# avr_programming_shield_Zif.net
KiCad netlist of a schematic drawn in EAGLE
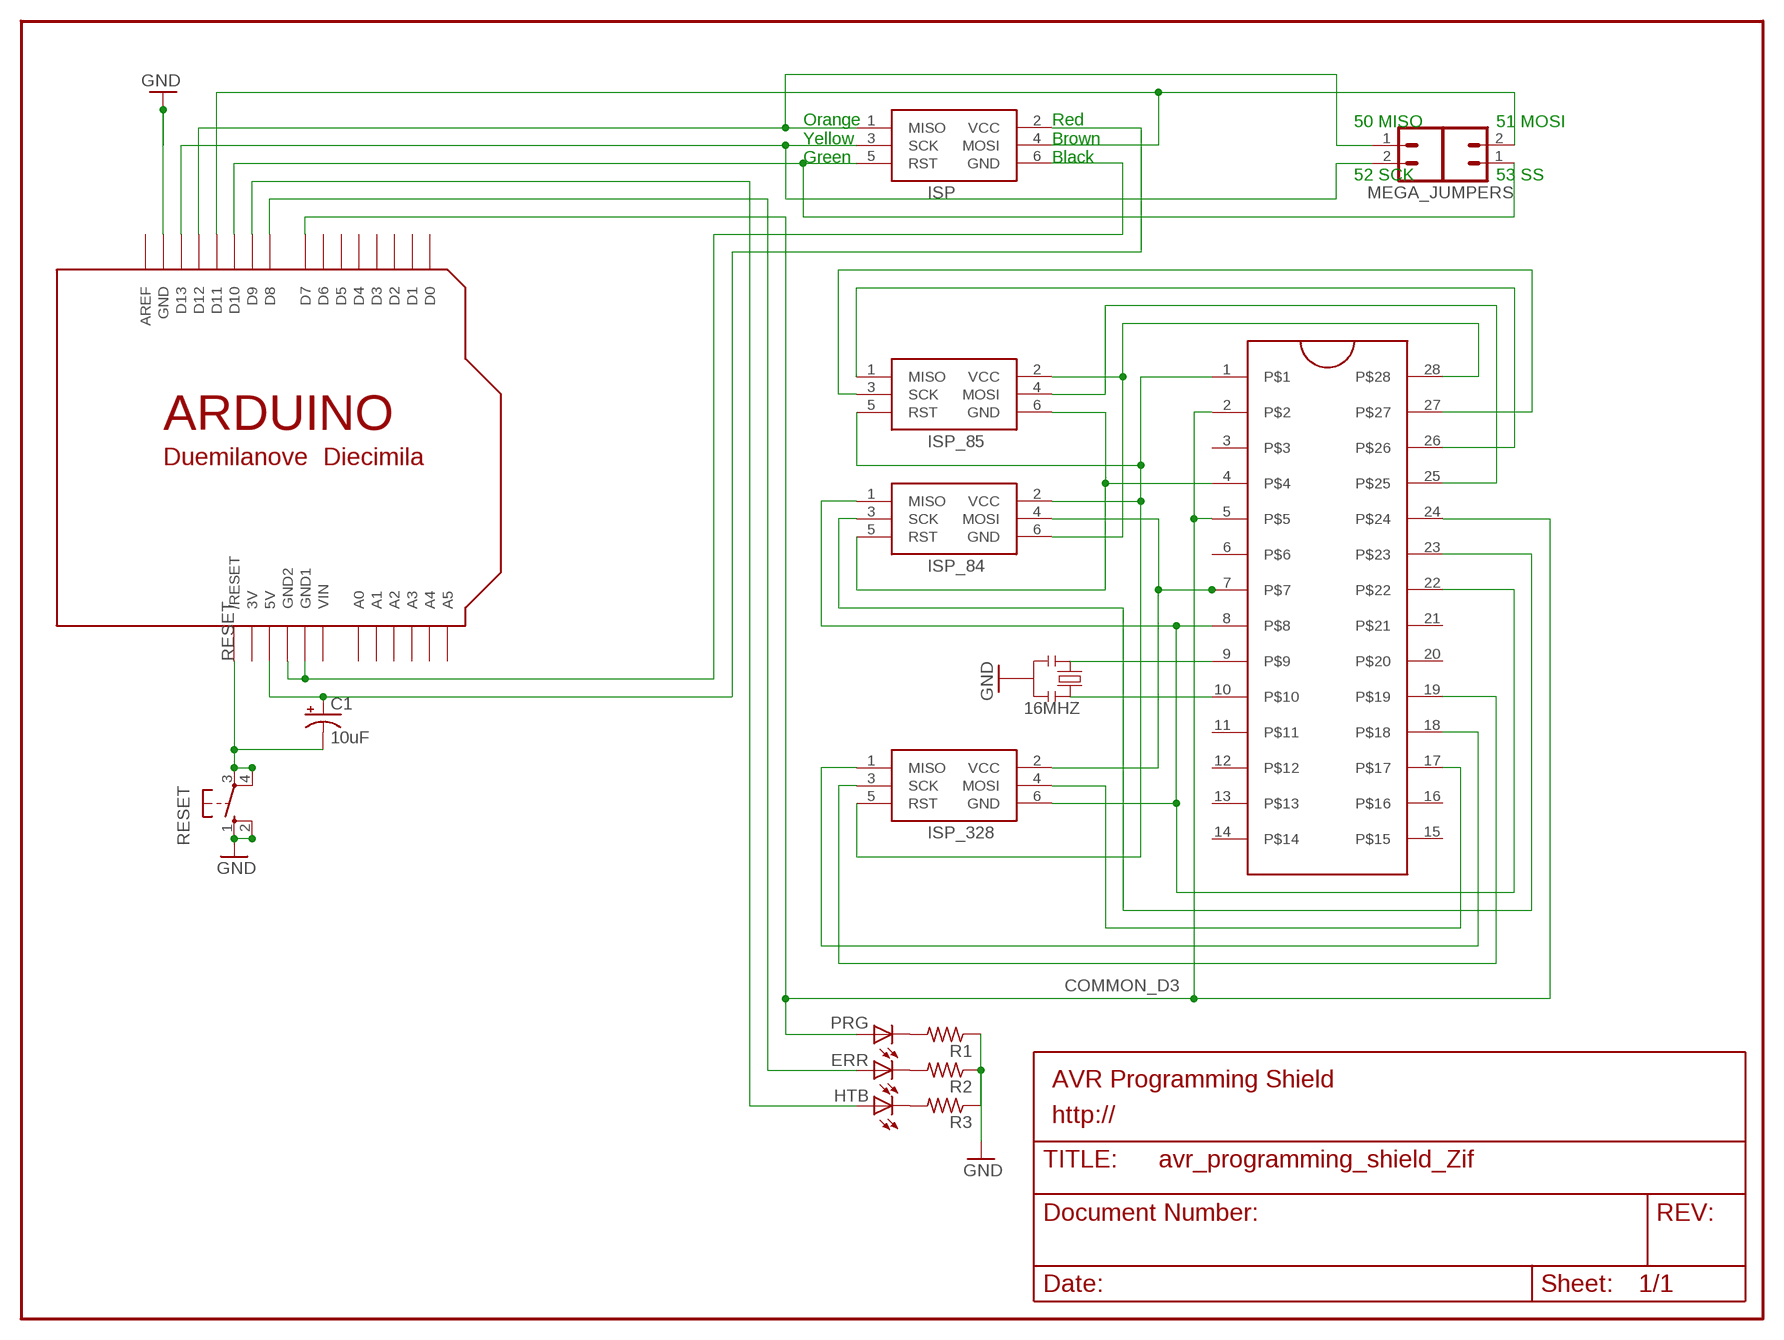
[diagram p0: schematic, sheet 1]

(export (version "E")
  (design (tool "Eeschema 10.0.6"))
  (components
    (comp (ref "16MHZ")
      (value "RESONATORPTH")
      (footprint "eagle-import:RESONATOR-PTH")
      (libsource (lib "eagle-import") (part "RESONATORPTH"))
    )
    (comp (ref "C1")
      (value "10uF")
      (footprint "eagle-import:CPOL-RADIAL-10UF-25V")
      (libsource (lib "eagle-import") (part "CAP_POLPTH2"))
    )
    (comp (ref "ERR")
      (value "LED3MM")
      (footprint "eagle-import:LED3MM")
      (libsource (lib "eagle-import") (part "LED3MM"))
    )
    (comp (ref "HTB")
      (value "LED3MM")
      (footprint "eagle-import:LED3MM")
      (libsource (lib "eagle-import") (part "LED3MM"))
    )
    (comp (ref "ISP")
      (value "AVRISP-6")
      (footprint "eagle-import:AVRISP")
      (libsource (lib "eagle-import") (part "AVRISP-6"))
    )
    (comp (ref "ISP_84")
      (value "AVRISP-6")
      (footprint "eagle-import:AVRISP")
      (libsource (lib "eagle-import") (part "AVRISP-6"))
    )
    (comp (ref "ISP_85")
      (value "AVRISP-6")
      (footprint "eagle-import:AVRISP")
      (libsource (lib "eagle-import") (part "AVRISP-6"))
    )
    (comp (ref "ISP_328")
      (value "AVRISP-6")
      (footprint "eagle-import:AVRISP")
      (libsource (lib "eagle-import") (part "AVRISP-6"))
    )
    (comp (ref "JP2")
      (value "M02PTH")
      (footprint "eagle-import:1X02")
      (libsource (lib "eagle-import") (part "M02PTH"))
    )
    (comp (ref "MEGA_JUMPERS")
      (value "M02PTH")
      (footprint "eagle-import:1X02")
      (libsource (lib "eagle-import") (part "M02PTH"))
    )
    (comp (ref "PRG")
      (value "LED3MM")
      (footprint "eagle-import:LED3MM")
      (libsource (lib "eagle-import") (part "LED3MM"))
    )
    (comp (ref "R1")
      (value "R-US_0204/2V")
      (footprint "eagle-import:0204V")
      (libsource (lib "eagle-import") (part "R-US_0204/2V"))
    )
    (comp (ref "R2")
      (value "R-US_0204/2V")
      (footprint "eagle-import:0204V")
      (libsource (lib "eagle-import") (part "R-US_0204/2V"))
    )
    (comp (ref "R3")
      (value "R-US_0204/2V")
      (footprint "eagle-import:0204V")
      (libsource (lib "eagle-import") (part "R-US_0204/2V"))
    )
    (comp (ref "RESET")
      (value "10-XX")
      (footprint "eagle-import:B3F-10XX")
      (libsource (lib "eagle-import") (part "10-XX"))
    )
    (comp (ref "U$1")
      (value "ARDUINO-NOHOLE")
      (footprint "eagle-import:ARDUINO-NOHOLE")
      (libsource (lib "eagle-import") (part "ARDUINO-NOHOLE"))
    )
    (comp (ref "U$2")
      (value "ZIFSOCKET-28-3ZIFFSOCKET-28-3")
      (footprint "eagle-import:DIL28-3-ZIF_SOCKET")
      (libsource (lib "eagle-import") (part "ZIFSOCKET-28-3ZIFFSOCKET-28-3"))
    )
  )
  (nets
    (net (code "1") (name "/3V") (class "Default")
      (node (ref "U$1") (pin "3V") (pinfunction "3V_3V") (pintype "power_in"))
    )
    (net (code "2") (name "/COMMON_D3") (class "Default")
      (node (ref "PRG") (pin "A") (pinfunction "A_A") (pintype "passive"))
      (node (ref "U$1") (pin "D7") (pinfunction "D7_D7") (pintype "bidirectional"))
      (node (ref "U$2") (pin "2") (pinfunction "P$2_2") (pintype "bidirectional"))
      (node (ref "U$2") (pin "24") (pinfunction "P$24_24") (pintype "bidirectional"))
      (node (ref "U$2") (pin "5") (pinfunction "P$5_5") (pintype "bidirectional"))
    )
    (net (code "3") (name "/RESET") (class "Default")
      (node (ref "C1") (pin "2") (pinfunction "-_2") (pintype "passive"))
      (node (ref "RESET") (pin "3") (pinfunction "P_3") (pintype "passive"))
      (node (ref "RESET") (pin "4") (pinfunction "P1_4") (pintype "passive"))
      (node (ref "U$1") (pin "RESET") (pinfunction "/RESET_RESET") (pintype "bidirectional"))
    )
    (net (code "4") (name "/VIN") (class "Default")
      (node (ref "U$1") (pin "VIN") (pinfunction "VIN_VIN") (pintype "power_in"))
    )
    (net (code "5") (name "GND") (class "Default")
      (node (ref "16MHZ") (pin "2") (pinfunction "2_2") (pintype "passive"))
      (node (ref "ISP") (pin "6") (pinfunction "GND_6") (pintype "power_in"))
      (node (ref "R1") (pin "1") (pinfunction "1_1") (pintype "passive"))
      (node (ref "R2") (pin "1") (pinfunction "1_1") (pintype "passive"))
      (node (ref "R3") (pin "1") (pinfunction "1_1") (pintype "passive"))
      (node (ref "RESET") (pin "1") (pinfunction "S_1") (pintype "passive"))
      (node (ref "RESET") (pin "2") (pinfunction "S1_2") (pintype "passive"))
      (node (ref "U$1") (pin "GND") (pinfunction "GND_GND") (pintype "power_in"))
      (node (ref "U$1") (pin "GND1") (pinfunction "GND1_GND1") (pintype "power_in"))
      (node (ref "U$1") (pin "GND2") (pinfunction "GND2_GND2") (pintype "power_in"))
    )
    (net (code "6") (name "Net-(C1-+)") (class "Default")
      (node (ref "C1") (pin "1") (pinfunction "+_1") (pintype "passive"))
      (node (ref "ISP") (pin "2") (pinfunction "VCC_2") (pintype "power_in"))
      (node (ref "U$1") (pin "5V") (pinfunction "5V_5V") (pintype "power_in"))
    )
    (net (code "7") (name "Net-(ERR-C)") (class "Default")
      (node (ref "ERR") (pin "K") (pinfunction "C_K") (pintype "passive"))
      (node (ref "R2") (pin "2") (pinfunction "2_2") (pintype "passive"))
    )
    (net (code "8") (name "Net-(ERR-PadA)") (class "Default")
      (node (ref "ERR") (pin "A") (pinfunction "A_A") (pintype "passive"))
      (node (ref "U$1") (pin "D8") (pinfunction "D8_D8") (pintype "bidirectional"))
    )
    (net (code "9") (name "Net-(HTB-C)") (class "Default")
      (node (ref "HTB") (pin "K") (pinfunction "C_K") (pintype "passive"))
      (node (ref "R3") (pin "2") (pinfunction "2_2") (pintype "passive"))
    )
    (net (code "10") (name "Net-(HTB-PadA)") (class "Default")
      (node (ref "HTB") (pin "A") (pinfunction "A_A") (pintype "passive"))
      (node (ref "U$1") (pin "D9") (pinfunction "D9_D9") (pintype "bidirectional"))
    )
    (net (code "11") (name "Net-(ISP-MISO)") (class "Default")
      (node (ref "ISP") (pin "1") (pinfunction "MISO_1") (pintype "input"))
      (node (ref "MEGA_JUMPERS") (pin "1") (pinfunction "1_1") (pintype "passive"))
      (node (ref "U$1") (pin "D12") (pinfunction "D12_D12") (pintype "bidirectional"))
    )
    (net (code "12") (name "Net-(ISP-MOSI)") (class "Default")
      (node (ref "ISP") (pin "4") (pinfunction "MOSI_4") (pintype "output"))
      (node (ref "JP2") (pin "2") (pinfunction "2_2") (pintype "passive"))
      (node (ref "U$1") (pin "D11") (pinfunction "D11_D11") (pintype "bidirectional"))
    )
    (net (code "13") (name "Net-(ISP-RST)") (class "Default")
      (node (ref "ISP") (pin "5") (pinfunction "RST_5") (pintype "output"))
      (node (ref "JP2") (pin "1") (pinfunction "1_1") (pintype "passive"))
      (node (ref "U$1") (pin "D10") (pinfunction "D10_D10") (pintype "bidirectional"))
    )
    (net (code "14") (name "Net-(ISP-SCK)") (class "Default")
      (node (ref "ISP") (pin "3") (pinfunction "SCK_3") (pintype "output"))
      (node (ref "MEGA_JUMPERS") (pin "2") (pinfunction "2_2") (pintype "passive"))
      (node (ref "U$1") (pin "D13") (pinfunction "D13_D13") (pintype "bidirectional"))
    )
    (net (code "15") (name "Net-(ISP_84-GND)") (class "Default")
      (node (ref "ISP_84") (pin "6") (pinfunction "GND_6") (pintype "power_in"))
      (node (ref "ISP_85") (pin "2") (pinfunction "VCC_2") (pintype "power_in"))
      (node (ref "U$2") (pin "28") (pinfunction "P$28_28") (pintype "bidirectional"))
    )
    (net (code "16") (name "Net-(ISP_84-RST)") (class "Default")
      (node (ref "ISP_84") (pin "5") (pinfunction "RST_5") (pintype "output"))
      (node (ref "ISP_85") (pin "6") (pinfunction "GND_6") (pintype "power_in"))
      (node (ref "U$2") (pin "4") (pinfunction "P$4_4") (pintype "bidirectional"))
    )
    (net (code "17") (name "Net-(ISP_84-SCK)") (class "Default")
      (node (ref "ISP_84") (pin "3") (pinfunction "SCK_3") (pintype "output"))
      (node (ref "U$2") (pin "23") (pinfunction "P$23_23") (pintype "bidirectional"))
    )
    (net (code "18") (name "Net-(ISP_85-MISO)") (class "Default")
      (node (ref "ISP_85") (pin "1") (pinfunction "MISO_1") (pintype "input"))
      (node (ref "U$2") (pin "26") (pinfunction "P$26_26") (pintype "bidirectional"))
    )
    (net (code "19") (name "Net-(ISP_85-MOSI)") (class "Default")
      (node (ref "ISP_85") (pin "4") (pinfunction "MOSI_4") (pintype "output"))
      (node (ref "U$2") (pin "25") (pinfunction "P$25_25") (pintype "bidirectional"))
    )
    (net (code "20") (name "Net-(ISP_85-SCK)") (class "Default")
      (node (ref "ISP_85") (pin "3") (pinfunction "SCK_3") (pintype "output"))
      (node (ref "U$2") (pin "27") (pinfunction "P$27_27") (pintype "bidirectional"))
    )
    (net (code "21") (name "Net-(ISP_328-GND)") (class "Default")
      (node (ref "ISP_328") (pin "6") (pinfunction "GND_6") (pintype "power_in"))
      (node (ref "ISP_84") (pin "1") (pinfunction "MISO_1") (pintype "input"))
      (node (ref "U$2") (pin "22") (pinfunction "P$22_22") (pintype "bidirectional"))
      (node (ref "U$2") (pin "8") (pinfunction "P$8_8") (pintype "bidirectional"))
    )
    (net (code "22") (name "Net-(ISP_328-MISO)") (class "Default")
      (node (ref "ISP_328") (pin "1") (pinfunction "MISO_1") (pintype "input"))
      (node (ref "U$2") (pin "18") (pinfunction "P$18_18") (pintype "bidirectional"))
    )
    (net (code "23") (name "Net-(ISP_328-MOSI)") (class "Default")
      (node (ref "ISP_328") (pin "4") (pinfunction "MOSI_4") (pintype "output"))
      (node (ref "U$2") (pin "17") (pinfunction "P$17_17") (pintype "bidirectional"))
    )
    (net (code "24") (name "Net-(ISP_328-RST)") (class "Default")
      (node (ref "ISP_328") (pin "5") (pinfunction "RST_5") (pintype "output"))
      (node (ref "ISP_84") (pin "2") (pinfunction "VCC_2") (pintype "power_in"))
      (node (ref "ISP_85") (pin "5") (pinfunction "RST_5") (pintype "output"))
      (node (ref "U$2") (pin "1") (pinfunction "P$1_1") (pintype "bidirectional"))
    )
    (net (code "25") (name "Net-(ISP_328-SCK)") (class "Default")
      (node (ref "ISP_328") (pin "3") (pinfunction "SCK_3") (pintype "output"))
      (node (ref "U$2") (pin "19") (pinfunction "P$19_19") (pintype "bidirectional"))
    )
    (net (code "26") (name "Net-(ISP_328-VCC)") (class "Default")
      (node (ref "ISP_328") (pin "2") (pinfunction "VCC_2") (pintype "power_in"))
      (node (ref "ISP_84") (pin "4") (pinfunction "MOSI_4") (pintype "output"))
      (node (ref "U$2") (pin "7") (pinfunction "P$7_7") (pintype "bidirectional"))
    )
    (net (code "27") (name "Net-(PRG-C)") (class "Default")
      (node (ref "PRG") (pin "K") (pinfunction "C_K") (pintype "passive"))
      (node (ref "R1") (pin "2") (pinfunction "2_2") (pintype "passive"))
    )
    (net (code "28") (name "Net-(U$2-P$9)") (class "Default")
      (node (ref "16MHZ") (pin "1") (pinfunction "1_1") (pintype "passive"))
      (node (ref "U$2") (pin "9") (pinfunction "P$9_9") (pintype "bidirectional"))
    )
    (net (code "29") (name "Net-(U$2-P$10)") (class "Default")
      (node (ref "16MHZ") (pin "3") (pinfunction "3_3") (pintype "passive"))
      (node (ref "U$2") (pin "10") (pinfunction "P$10_10") (pintype "bidirectional"))
    )
    (net (code "30") (name "unconnected-(U$1-PadA0)") (class "Default")
      (node (ref "U$1") (pin "A0") (pinfunction "A0_A0") (pintype "bidirectional"))
    )
    (net (code "31") (name "unconnected-(U$1-PadA1)") (class "Default")
      (node (ref "U$1") (pin "A1") (pinfunction "A1_A1") (pintype "bidirectional"))
    )
    (net (code "32") (name "unconnected-(U$1-PadA2)") (class "Default")
      (node (ref "U$1") (pin "A2") (pinfunction "A2_A2") (pintype "bidirectional"))
    )
    (net (code "33") (name "unconnected-(U$1-PadA3)") (class "Default")
      (node (ref "U$1") (pin "A3") (pinfunction "A3_A3") (pintype "bidirectional"))
    )
    (net (code "34") (name "unconnected-(U$1-PadA4)") (class "Default")
      (node (ref "U$1") (pin "A4") (pinfunction "A4_A4") (pintype "bidirectional"))
    )
    (net (code "35") (name "unconnected-(U$1-PadA5)") (class "Default")
      (node (ref "U$1") (pin "A5") (pinfunction "A5_A5") (pintype "bidirectional"))
    )
    (net (code "36") (name "unconnected-(U$1-PadAREF)") (class "Default")
      (node (ref "U$1") (pin "AREF") (pinfunction "AREF_AREF") (pintype "bidirectional"))
    )
    (net (code "37") (name "unconnected-(U$1-PadD0)") (class "Default")
      (node (ref "U$1") (pin "D0") (pinfunction "D0_D0") (pintype "bidirectional"))
    )
    (net (code "38") (name "unconnected-(U$1-PadD1)") (class "Default")
      (node (ref "U$1") (pin "D1") (pinfunction "D1_D1") (pintype "bidirectional"))
    )
    (net (code "39") (name "unconnected-(U$1-PadD2)") (class "Default")
      (node (ref "U$1") (pin "D2") (pinfunction "D2_D2") (pintype "bidirectional"))
    )
    (net (code "40") (name "unconnected-(U$1-PadD3)") (class "Default")
      (node (ref "U$1") (pin "D3") (pinfunction "D3_D3") (pintype "bidirectional"))
    )
    (net (code "41") (name "unconnected-(U$1-PadD4)") (class "Default")
      (node (ref "U$1") (pin "D4") (pinfunction "D4_D4") (pintype "bidirectional"))
    )
    (net (code "42") (name "unconnected-(U$1-PadD5)") (class "Default")
      (node (ref "U$1") (pin "D5") (pinfunction "D5_D5") (pintype "bidirectional"))
    )
    (net (code "43") (name "unconnected-(U$1-PadD6)") (class "Default")
      (node (ref "U$1") (pin "D6") (pinfunction "D6_D6") (pintype "bidirectional"))
    )
    (net (code "44") (name "unconnected-(U$2-P$3-Pad3)") (class "Default")
      (node (ref "U$2") (pin "3") (pinfunction "P$3_3") (pintype "bidirectional"))
    )
    (net (code "45") (name "unconnected-(U$2-P$6-Pad6)") (class "Default")
      (node (ref "U$2") (pin "6") (pinfunction "P$6_6") (pintype "bidirectional"))
    )
    (net (code "46") (name "unconnected-(U$2-P$11-Pad11)") (class "Default")
      (node (ref "U$2") (pin "11") (pinfunction "P$11_11") (pintype "bidirectional"))
    )
    (net (code "47") (name "unconnected-(U$2-P$12-Pad12)") (class "Default")
      (node (ref "U$2") (pin "12") (pinfunction "P$12_12") (pintype "bidirectional"))
    )
    (net (code "48") (name "unconnected-(U$2-P$13-Pad13)") (class "Default")
      (node (ref "U$2") (pin "13") (pinfunction "P$13_13") (pintype "bidirectional"))
    )
    (net (code "49") (name "unconnected-(U$2-P$14-Pad14)") (class "Default")
      (node (ref "U$2") (pin "14") (pinfunction "P$14_14") (pintype "bidirectional"))
    )
    (net (code "50") (name "unconnected-(U$2-P$15-Pad15)") (class "Default")
      (node (ref "U$2") (pin "15") (pinfunction "P$15_15") (pintype "bidirectional"))
    )
    (net (code "51") (name "unconnected-(U$2-P$16-Pad16)") (class "Default")
      (node (ref "U$2") (pin "16") (pinfunction "P$16_16") (pintype "bidirectional"))
    )
    (net (code "52") (name "unconnected-(U$2-P$20-Pad20)") (class "Default")
      (node (ref "U$2") (pin "20") (pinfunction "P$20_20") (pintype "bidirectional"))
    )
    (net (code "53") (name "unconnected-(U$2-P$21-Pad21)") (class "Default")
      (node (ref "U$2") (pin "21") (pinfunction "P$21_21") (pintype "bidirectional"))
    )
  )
)
